# Yugocade.net
KiCad netlist of a schematic drawn in EAGLE
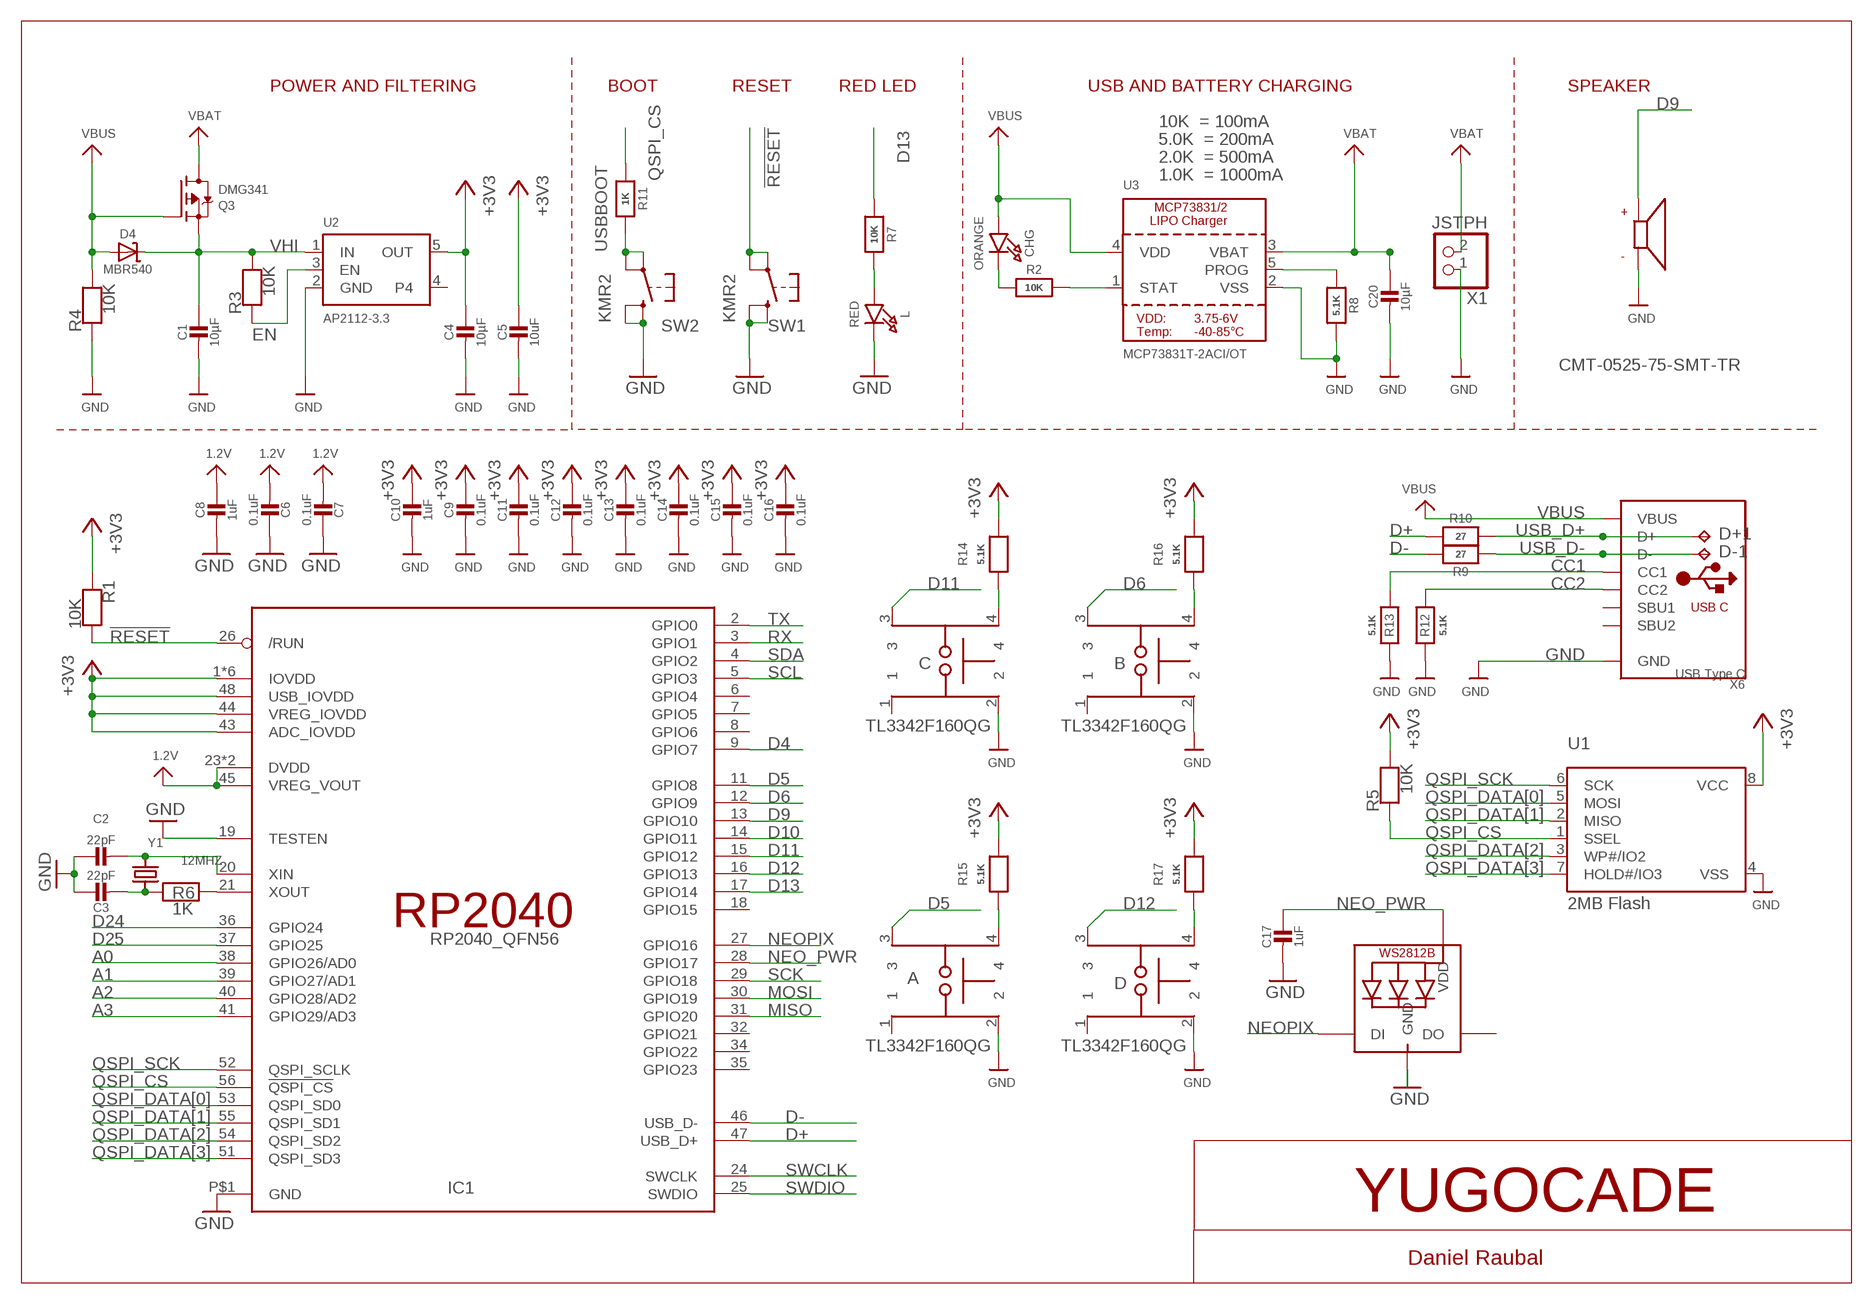
[diagram p0: schematic, sheet 1]

(export (version "E")
  (design (tool "Eeschema 10.0.6"))
  (components
    (comp (ref "A")
      (value "TL3342F160QG")
      (footprint "eagle-import:SW_TL3342F160QG")
      (fields (field (name "MF") "E-Switch"))
      (libsource (lib "eagle-import") (part "TL3342F160QG"))
    )
    (comp (ref "B")
      (value "TL3342F160QG")
      (footprint "eagle-import:SW_TL3342F160QG")
      (fields (field (name "MF") "E-Switch"))
      (libsource (lib "eagle-import") (part "TL3342F160QG"))
    )
    (comp (ref "C")
      (value "TL3342F160QG")
      (footprint "eagle-import:SW_TL3342F160QG")
      (fields (field (name "MF") "E-Switch"))
      (libsource (lib "eagle-import") (part "TL3342F160QG"))
    )
    (comp (ref "C1")
      (value "10µF")
      (footprint "eagle-import:0805-NO")
      (libsource (lib "eagle-import") (part "CAP_CERAMIC0805-NOOUTLINE"))
    )
    (comp (ref "C2")
      (value "22pF")
      (footprint "eagle-import:0603-NO")
      (libsource (lib "eagle-import") (part "CAP_CERAMIC0603_NO"))
    )
    (comp (ref "C3")
      (value "22pF")
      (footprint "eagle-import:0603-NO")
      (libsource (lib "eagle-import") (part "CAP_CERAMIC0603_NO"))
    )
    (comp (ref "C4")
      (value "10µF")
      (footprint "eagle-import:0805-NO")
      (fields (field (name "REV") "A"))
      (libsource (lib "eagle-import") (part "CAP_CERAMIC0805-NOOUTLINE"))
    )
    (comp (ref "C5")
      (value "10uF")
      (footprint "eagle-import:0805-NO")
      (libsource (lib "eagle-import") (part "CAP_CERAMIC0805-NOOUTLINE"))
    )
    (comp (ref "C6")
      (value "0.1uF")
      (footprint "eagle-import:0603-NO")
      (libsource (lib "eagle-import") (part "CAP_CERAMIC0603_NO"))
    )
    (comp (ref "C7")
      (value "0.1uF")
      (footprint "eagle-import:0603-NO")
      (libsource (lib "eagle-import") (part "CAP_CERAMIC0603_NO"))
    )
    (comp (ref "C8")
      (value "1uF")
      (footprint "eagle-import:0603-NO")
      (libsource (lib "eagle-import") (part "CAP_CERAMIC0603_NO"))
    )
    (comp (ref "C9")
      (value "0.1uF")
      (footprint "eagle-import:0603-NO")
      (libsource (lib "eagle-import") (part "CAP_CERAMIC0603_NO"))
    )
    (comp (ref "C10")
      (value "1uF")
      (footprint "eagle-import:0603-NO")
      (libsource (lib "eagle-import") (part "CAP_CERAMIC0603_NO"))
    )
    (comp (ref "C11")
      (value "0.1uF")
      (footprint "eagle-import:0603-NO")
      (libsource (lib "eagle-import") (part "CAP_CERAMIC0603_NO"))
    )
    (comp (ref "C12")
      (value "0.1uF")
      (footprint "eagle-import:0603-NO")
      (libsource (lib "eagle-import") (part "CAP_CERAMIC0603_NO"))
    )
    (comp (ref "C13")
      (value "0.1uF")
      (footprint "eagle-import:0603-NO")
      (libsource (lib "eagle-import") (part "CAP_CERAMIC0603_NO"))
    )
    (comp (ref "C14")
      (value "0.1uF")
      (footprint "eagle-import:0603-NO")
      (libsource (lib "eagle-import") (part "CAP_CERAMIC0603_NO"))
    )
    (comp (ref "C15")
      (value "0.1uF")
      (footprint "eagle-import:0603-NO")
      (libsource (lib "eagle-import") (part "CAP_CERAMIC0603_NO"))
    )
    (comp (ref "C16")
      (value "0.1uF")
      (footprint "eagle-import:0603-NO")
      (libsource (lib "eagle-import") (part "CAP_CERAMIC0603_NO"))
    )
    (comp (ref "C17")
      (value "1uF")
      (footprint "eagle-import:0603-NO")
      (libsource (lib "eagle-import") (part "CAP_CERAMIC0603_NO"))
    )
    (comp (ref "C20")
      (value "10µF")
      (footprint "eagle-import:0805-NO")
      (libsource (lib "eagle-import") (part "CAP_CERAMIC0805-NOOUTLINE"))
    )
    (comp (ref "CHG")
      (value "ORANGE")
      (footprint "eagle-import:CHIPLED_0603_NOOUTLINE")
      (libsource (lib "eagle-import") (part "LED0603_NOOUTLINE"))
    )
    (comp (ref "D")
      (value "TL3342F160QG")
      (footprint "eagle-import:SW_TL3342F160QG")
      (fields (field (name "MF") "E-Switch"))
      (libsource (lib "eagle-import") (part "TL3342F160QG"))
    )
    (comp (ref "D+1")
      (value "TPB1,27")
      (footprint "eagle-import:B1,27")
      (libsource (lib "eagle-import") (part "TPB1,27"))
    )
    (comp (ref "D-1")
      (value "TPB1,27")
      (footprint "eagle-import:B1,27")
      (libsource (lib "eagle-import") (part "TPB1,27"))
    )
    (comp (ref "D4")
      (value "MBR540")
      (footprint "eagle-import:SOD-123")
      (libsource (lib "eagle-import") (part "DIODE-SCHOTTKYSOD-123"))
    )
    (comp (ref "IC1")
      (value "RP2040_QFN56")
      (footprint "eagle-import:QFN56_7MM_REDUCEDEPAD")
      (libsource (lib "eagle-import") (part "RP2040_QFN56"))
    )
    (comp (ref "L")
      (value "RED")
      (footprint "eagle-import:CHIPLED_0603_NOOUTLINE")
      (libsource (lib "eagle-import") (part "LED0603_NOOUTLINE"))
    )
    (comp (ref "LED1")
      (value "WS2812B3535")
      (footprint "eagle-import:LED3535")
      (libsource (lib "eagle-import") (part "WS2812B3535"))
    )
    (comp (ref "LS1")
      (value "CMT-0525-75-SMT-TR")
      (footprint "eagle-import:XDCR_CMT-0525-75-SMT-TR")
      (fields (field (name "MF") "CUI Devices"))
      (libsource (lib "eagle-import") (part "CMT-0525-75-SMT-TR"))
    )
    (comp (ref "Q3")
      (value "DMG341")
      (footprint "eagle-import:SOT23-R")
      (libsource (lib "eagle-import") (part "MOSFET-P"))
    )
    (comp (ref "R1")
      (value "10K")
      (footprint "eagle-import:0603-NO")
      (libsource (lib "eagle-import") (part "RESISTOR_0603_NOOUT"))
    )
    (comp (ref "R2")
      (value "10K")
      (footprint "eagle-import:0603-NO")
      (libsource (lib "eagle-import") (part "RESISTOR_0603_NOOUT"))
    )
    (comp (ref "R3")
      (value "10K")
      (footprint "eagle-import:0603-NO")
      (libsource (lib "eagle-import") (part "RESISTOR_0603_NOOUT"))
    )
    (comp (ref "R4")
      (value "10K")
      (footprint "eagle-import:0603-NO")
      (libsource (lib "eagle-import") (part "RESISTOR_0603_NOOUT"))
    )
    (comp (ref "R5")
      (value "10K")
      (footprint "eagle-import:0603-NO")
      (libsource (lib "eagle-import") (part "RESISTOR_0603_NOOUT"))
    )
    (comp (ref "R6")
      (value "1K")
      (footprint "eagle-import:0603-NO")
      (libsource (lib "eagle-import") (part "RESISTOR_0603_NOOUT"))
    )
    (comp (ref "R7")
      (value "10K")
      (footprint "eagle-import:0603-NO")
      (libsource (lib "eagle-import") (part "RESISTOR_0603_NOOUT"))
    )
    (comp (ref "R8")
      (value "5.1K")
      (footprint "eagle-import:0603-NO")
      (libsource (lib "eagle-import") (part "RESISTOR_0603_NOOUT"))
    )
    (comp (ref "R9")
      (value "27")
      (footprint "eagle-import:0603-NO")
      (libsource (lib "eagle-import") (part "RESISTOR_0603_NOOUT"))
    )
    (comp (ref "R10")
      (value "27")
      (footprint "eagle-import:0603-NO")
      (libsource (lib "eagle-import") (part "RESISTOR_0603_NOOUT"))
    )
    (comp (ref "R11")
      (value "1K")
      (footprint "eagle-import:0603-NO")
      (libsource (lib "eagle-import") (part "RESISTOR_0603_NOOUT"))
    )
    (comp (ref "R12")
      (value "5.1K")
      (footprint "eagle-import:0603-NO")
      (libsource (lib "eagle-import") (part "RESISTOR_0603_NOOUT"))
    )
    (comp (ref "R13")
      (value "5.1K")
      (footprint "eagle-import:0603-NO")
      (libsource (lib "eagle-import") (part "RESISTOR_0603_NOOUT"))
    )
    (comp (ref "R14")
      (value "5.1K")
      (footprint "eagle-import:0603-NO")
      (libsource (lib "eagle-import") (part "RESISTOR_0603_NOOUT"))
    )
    (comp (ref "R15")
      (value "5.1K")
      (footprint "eagle-import:0603-NO")
      (libsource (lib "eagle-import") (part "RESISTOR_0603_NOOUT"))
    )
    (comp (ref "R16")
      (value "5.1K")
      (footprint "eagle-import:0603-NO")
      (libsource (lib "eagle-import") (part "RESISTOR_0603_NOOUT"))
    )
    (comp (ref "R17")
      (value "5.1K")
      (footprint "eagle-import:0603-NO")
      (libsource (lib "eagle-import") (part "RESISTOR_0603_NOOUT"))
    )
    (comp (ref "SW1")
      (value "KMR2")
      (footprint "eagle-import:BTN_KMR2_4.6X2.8")
      (libsource (lib "eagle-import") (part "SWITCH_TACT_SMT4.6X2.8"))
    )
    (comp (ref "SW2")
      (value "KMR2")
      (footprint "eagle-import:BTN_KMR2_4.6X2.8")
      (libsource (lib "eagle-import") (part "SWITCH_TACT_SMT4.6X2.8"))
    )
    (comp (ref "U1")
      (value "2MB Flash")
      (footprint "eagle-import:SOIC8_208MIL")
      (libsource (lib "eagle-import") (part "SPIFLASH_8PIN208MIL"))
    )
    (comp (ref "U2")
      (value "AP2112-3.3")
      (footprint "eagle-import:SOT23-5@1")
      (libsource (lib "eagle-import") (part "VREG_SOT23-5"))
    )
    (comp (ref "U3")
      (value "MCP73831T-2ACI/OT")
      (footprint "eagle-import:SOT23-5")
      (libsource (lib "eagle-import") (part "MCP73831/2"))
    )
    (comp (ref "X1")
      (value "JSTPH")
      (footprint "eagle-import:JSTPH2_BATT")
      (libsource (lib "eagle-import") (part "CON_JST_PH_2PIN_BATT"))
    )
    (comp (ref "X6")
      (value "USB Type C")
      (footprint "eagle-import:USB_C_CUSB31-CFM2AX-01-X")
      (libsource (lib "eagle-import") (part "USB_C"))
    )
    (comp (ref "Y1")
      (value "12MHZ")
      (footprint "eagle-import:CRYSTAL_2.5X2")
      (libsource (lib "eagle-import") (part "CRYSTAL2.5X2.0"))
    )
  )
  (nets
    (net (code "1") (name "+3V3") (class "Default")
      (node (ref "C10") (pin "1") (pinfunction "1_1") (pintype "passive"))
      (node (ref "C11") (pin "1") (pinfunction "1_1") (pintype "passive"))
      (node (ref "C12") (pin "1") (pinfunction "1_1") (pintype "passive"))
      (node (ref "C13") (pin "1") (pinfunction "1_1") (pintype "passive"))
      (node (ref "C14") (pin "1") (pinfunction "1_1") (pintype "passive"))
      (node (ref "C15") (pin "1") (pinfunction "1_1") (pintype "passive"))
      (node (ref "C16") (pin "1") (pinfunction "1_1") (pintype "passive"))
      (node (ref "C4") (pin "1") (pinfunction "1_1") (pintype "passive"))
      (node (ref "C5") (pin "1") (pinfunction "1_1") (pintype "passive"))
      (node (ref "C9") (pin "1") (pinfunction "1_1") (pintype "passive"))
      (node (ref "IC1") (pin "1") (pinfunction "IOVDD_1") (pintype "power_in"))
      (node (ref "IC1") (pin "10") (pinfunction "IOVDD_10") (pintype "power_in"))
      (node (ref "IC1") (pin "22") (pinfunction "IOVDD_22") (pintype "power_in"))
      (node (ref "IC1") (pin "33") (pinfunction "IOVDD_33") (pintype "power_in"))
      (node (ref "IC1") (pin "42") (pinfunction "IOVDD_42") (pintype "power_in"))
      (node (ref "IC1") (pin "43") (pinfunction "ADC_IOVDD_43") (pintype "power_in"))
      (node (ref "IC1") (pin "44") (pinfunction "VREG_IOVDD_44") (pintype "power_in"))
      (node (ref "IC1") (pin "48") (pinfunction "USB_IOVDD_48") (pintype "power_in"))
      (node (ref "IC1") (pin "49") (pinfunction "IOVDD_49") (pintype "power_in"))
      (node (ref "R1") (pin "1") (pinfunction "1_1") (pintype "passive"))
      (node (ref "R14") (pin "1") (pinfunction "1_1") (pintype "passive"))
      (node (ref "R15") (pin "1") (pinfunction "1_1") (pintype "passive"))
      (node (ref "R16") (pin "1") (pinfunction "1_1") (pintype "passive"))
      (node (ref "R17") (pin "1") (pinfunction "1_1") (pintype "passive"))
      (node (ref "R5") (pin "2") (pinfunction "2_2") (pintype "passive"))
      (node (ref "U1") (pin "8") (pinfunction "VCC_8") (pintype "bidirectional"))
      (node (ref "U2") (pin "5") (pinfunction "OUT_5") (pintype "power_in"))
    )
    (net (code "2") (name "/A0") (class "Default")
      (node (ref "IC1") (pin "38") (pinfunction "GPIO26/AD0_38") (pintype "bidirectional"))
    )
    (net (code "3") (name "/A1") (class "Default")
      (node (ref "IC1") (pin "39") (pinfunction "GPIO27/AD1_39") (pintype "bidirectional"))
    )
    (net (code "4") (name "/A2") (class "Default")
      (node (ref "IC1") (pin "40") (pinfunction "GPIO28/AD2_40") (pintype "bidirectional"))
    )
    (net (code "5") (name "/A3") (class "Default")
      (node (ref "IC1") (pin "41") (pinfunction "GPIO29/AD3_41") (pintype "bidirectional"))
    )
    (net (code "6") (name "/CC1") (class "Default")
      (node (ref "R13") (pin "2") (pinfunction "2_2") (pintype "passive"))
      (node (ref "X6") (pin "A5") (pinfunction "CC1_A5") (pintype "bidirectional"))
    )
    (net (code "7") (name "/CC2") (class "Default")
      (node (ref "R12") (pin "2") (pinfunction "2_2") (pintype "passive"))
      (node (ref "X6") (pin "B5") (pinfunction "CC2_B5") (pintype "bidirectional"))
    )
    (net (code "8") (name "/D+") (class "Default")
      (node (ref "IC1") (pin "47") (pinfunction "USB_D+_47") (pintype "bidirectional"))
      (node (ref "R10") (pin "2") (pinfunction "2_2") (pintype "passive"))
    )
    (net (code "9") (name "/D-") (class "Default")
      (node (ref "IC1") (pin "46") (pinfunction "USB_D-_46") (pintype "bidirectional"))
      (node (ref "R9") (pin "2") (pinfunction "2_2") (pintype "passive"))
    )
    (net (code "10") (name "/D4") (class "Default")
      (node (ref "IC1") (pin "9") (pinfunction "GPIO7_9") (pintype "bidirectional"))
    )
    (net (code "11") (name "/D5") (class "Default")
      (node (ref "A") (pin "3") (pinfunction "3_3") (pintype "passive"))
      (node (ref "IC1") (pin "11") (pinfunction "GPIO8_11") (pintype "bidirectional"))
    )
    (net (code "12") (name "/D6") (class "Default")
      (node (ref "B") (pin "3") (pinfunction "3_3") (pintype "passive"))
      (node (ref "IC1") (pin "12") (pinfunction "GPIO9_12") (pintype "bidirectional"))
    )
    (net (code "13") (name "/D9") (class "Default")
      (node (ref "IC1") (pin "13") (pinfunction "GPIO10_13") (pintype "bidirectional"))
      (node (ref "LS1") (pin "P") (pinfunction "P_P") (pintype "passive"))
    )
    (net (code "14") (name "/D10") (class "Default")
      (node (ref "IC1") (pin "14") (pinfunction "GPIO11_14") (pintype "bidirectional"))
    )
    (net (code "15") (name "/D11") (class "Default")
      (node (ref "C") (pin "3") (pinfunction "3_3") (pintype "passive"))
      (node (ref "IC1") (pin "15") (pinfunction "GPIO12_15") (pintype "bidirectional"))
    )
    (net (code "16") (name "/D12") (class "Default")
      (node (ref "D") (pin "3") (pinfunction "3_3") (pintype "passive"))
      (node (ref "IC1") (pin "16") (pinfunction "GPIO13_16") (pintype "bidirectional"))
    )
    (net (code "17") (name "/D13") (class "Default")
      (node (ref "IC1") (pin "17") (pinfunction "GPIO14_17") (pintype "bidirectional"))
      (node (ref "R7") (pin "1") (pinfunction "1_1") (pintype "passive"))
    )
    (net (code "18") (name "/D24") (class "Default")
      (node (ref "IC1") (pin "36") (pinfunction "GPIO24_36") (pintype "bidirectional"))
    )
    (net (code "19") (name "/D25") (class "Default")
      (node (ref "IC1") (pin "37") (pinfunction "GPIO25_37") (pintype "bidirectional"))
    )
    (net (code "20") (name "/EN") (class "Default")
      (node (ref "R3") (pin "1") (pinfunction "1_1") (pintype "passive"))
      (node (ref "U2") (pin "3") (pinfunction "EN_3") (pintype "input"))
    )
    (net (code "21") (name "/MISO") (class "Default")
      (node (ref "IC1") (pin "31") (pinfunction "GPIO20_31") (pintype "bidirectional"))
    )
    (net (code "22") (name "/MOSI") (class "Default")
      (node (ref "IC1") (pin "30") (pinfunction "GPIO19_30") (pintype "bidirectional"))
    )
    (net (code "23") (name "/NEOPIX") (class "Default")
      (node (ref "IC1") (pin "27") (pinfunction "GPIO16_27") (pintype "bidirectional"))
      (node (ref "LED1") (pin "1") (pinfunction "DI_1") (pintype "input"))
    )
    (net (code "24") (name "/NEO_PWR") (class "Default")
      (node (ref "C17") (pin "1") (pinfunction "1_1") (pintype "passive"))
      (node (ref "IC1") (pin "28") (pinfunction "GPIO17_28") (pintype "bidirectional"))
      (node (ref "LED1") (pin "2") (pinfunction "VDD_2") (pintype "power_in"))
    )
    (net (code "25") (name "/QSPI_CS") (class "Default")
      (node (ref "IC1") (pin "56") (pinfunction "~{QSPI_CS}_56") (pintype "bidirectional"))
      (node (ref "R11") (pin "1") (pinfunction "1_1") (pintype "passive"))
      (node (ref "R5") (pin "1") (pinfunction "1_1") (pintype "passive"))
      (node (ref "U1") (pin "1") (pinfunction "SSEL_1") (pintype "bidirectional"))
    )
    (net (code "26") (name "/QSPI_DATA[0]") (class "Default")
      (node (ref "IC1") (pin "53") (pinfunction "QSPI_SD0_53") (pintype "bidirectional"))
      (node (ref "U1") (pin "5") (pinfunction "MOSI_5") (pintype "bidirectional"))
    )
    (net (code "27") (name "/QSPI_DATA[1]") (class "Default")
      (node (ref "IC1") (pin "55") (pinfunction "QSPI_SD1_55") (pintype "bidirectional"))
      (node (ref "U1") (pin "2") (pinfunction "MISO_2") (pintype "bidirectional"))
    )
    (net (code "28") (name "/QSPI_DATA[2]") (class "Default")
      (node (ref "IC1") (pin "54") (pinfunction "QSPI_SD2_54") (pintype "bidirectional"))
      (node (ref "U1") (pin "3") (pinfunction "WP#/IO2_3") (pintype "bidirectional"))
    )
    (net (code "29") (name "/QSPI_DATA[3]") (class "Default")
      (node (ref "IC1") (pin "51") (pinfunction "QSPI_SD3_51") (pintype "bidirectional"))
      (node (ref "U1") (pin "7") (pinfunction "HOLD#/IO3_7") (pintype "bidirectional"))
    )
    (net (code "30") (name "/QSPI_SCK") (class "Default")
      (node (ref "IC1") (pin "52") (pinfunction "QSPI_SCLK_52") (pintype "bidirectional"))
      (node (ref "U1") (pin "6") (pinfunction "SCK_6") (pintype "bidirectional"))
    )
    (net (code "31") (name "/RX") (class "Default")
      (node (ref "IC1") (pin "3") (pinfunction "GPIO1_3") (pintype "bidirectional"))
    )
    (net (code "32") (name "/SCK") (class "Default")
      (node (ref "IC1") (pin "29") (pinfunction "GPIO18_29") (pintype "bidirectional"))
    )
    (net (code "33") (name "/SCL") (class "Default")
      (node (ref "IC1") (pin "5") (pinfunction "GPIO3_5") (pintype "bidirectional"))
    )
    (net (code "34") (name "/SDA") (class "Default")
      (node (ref "IC1") (pin "4") (pinfunction "GPIO2_4") (pintype "bidirectional"))
    )
    (net (code "35") (name "/SWCLK") (class "Default")
      (node (ref "IC1") (pin "24") (pinfunction "SWCLK_24") (pintype "bidirectional"))
    )
    (net (code "36") (name "/SWDIO") (class "Default")
      (node (ref "IC1") (pin "25") (pinfunction "SWDIO_25") (pintype "bidirectional"))
    )
    (net (code "37") (name "/TX") (class "Default")
      (node (ref "IC1") (pin "2") (pinfunction "GPIO0_2") (pintype "bidirectional"))
    )
    (net (code "38") (name "/USBBOOT") (class "Default")
      (node (ref "R11") (pin "2") (pinfunction "2_2") (pintype "passive"))
      (node (ref "SW2") (pin "A") (pinfunction "P_A") (pintype "passive"))
      (node (ref "SW2") (pin "A'") (pinfunction "P1_A'") (pintype "passive"))
    )
    (net (code "39") (name "/USB_D+") (class "Default")
      (node (ref "D+1") (pin "TP") (pinfunction "TP_TP") (pintype "input"))
      (node (ref "R10") (pin "1") (pinfunction "1_1") (pintype "passive"))
      (node (ref "X6") (pin "A6") (pinfunction "D+_A6") (pintype "bidirectional"))
      (node (ref "X6") (pin "B6") (pinfunction "D+_B6") (pintype "bidirectional"))
    )
    (net (code "40") (name "/USB_D-") (class "Default")
      (node (ref "D-1") (pin "TP") (pinfunction "TP_TP") (pintype "input"))
      (node (ref "R9") (pin "1") (pinfunction "1_1") (pintype "passive"))
      (node (ref "X6") (pin "A7") (pinfunction "D-_A7") (pintype "bidirectional"))
      (node (ref "X6") (pin "B7") (pinfunction "D-_B7") (pintype "bidirectional"))
    )
    (net (code "41") (name "/VHI") (class "Default")
      (node (ref "C1") (pin "1") (pinfunction "1_1") (pintype "passive"))
      (node (ref "D4") (pin "C") (pinfunction "C_C") (pintype "passive"))
      (node (ref "Q3") (pin "2") (pinfunction "S_2") (pintype "passive"))
      (node (ref "R3") (pin "2") (pinfunction "2_2") (pintype "passive"))
      (node (ref "U2") (pin "1") (pinfunction "IN_1") (pintype "power_in"))
    )
    (net (code "42") (name "/~{RESET}") (class "Default")
      (node (ref "IC1") (pin "26") (pinfunction "/RUN_26") (pintype "bidirectional"))
      (node (ref "R1") (pin "2") (pinfunction "2_2") (pintype "passive"))
      (node (ref "SW1") (pin "A") (pinfunction "P_A") (pintype "passive"))
      (node (ref "SW1") (pin "A'") (pinfunction "P1_A'") (pintype "passive"))
    )
    (net (code "43") (name "1.2V") (class "Default")
      (node (ref "C6") (pin "2") (pinfunction "2_2") (pintype "passive"))
      (node (ref "C7") (pin "2") (pinfunction "2_2") (pintype "passive"))
      (node (ref "C8") (pin "1") (pinfunction "1_1") (pintype "passive"))
      (node (ref "IC1") (pin "23") (pinfunction "DVDD_23") (pintype "power_in"))
      (node (ref "IC1") (pin "45") (pinfunction "VREG_VOUT_45") (pintype "power_in"))
      (node (ref "IC1") (pin "50") (pinfunction "DVDD_50") (pintype "power_in"))
    )
    (net (code "44") (name "GND") (class "Default")
      (node (ref "A") (pin "2") (pinfunction "2_2") (pintype "passive"))
      (node (ref "B") (pin "2") (pinfunction "2_2") (pintype "passive"))
      (node (ref "C") (pin "2") (pinfunction "2_2") (pintype "passive"))
      (node (ref "C1") (pin "2") (pinfunction "2_2") (pintype "passive"))
      (node (ref "C10") (pin "2") (pinfunction "2_2") (pintype "passive"))
      (node (ref "C11") (pin "2") (pinfunction "2_2") (pintype "passive"))
      (node (ref "C12") (pin "2") (pinfunction "2_2") (pintype "passive"))
      (node (ref "C13") (pin "2") (pinfunction "2_2") (pintype "passive"))
      (node (ref "C14") (pin "2") (pinfunction "2_2") (pintype "passive"))
      (node (ref "C15") (pin "2") (pinfunction "2_2") (pintype "passive"))
      (node (ref "C16") (pin "2") (pinfunction "2_2") (pintype "passive"))
      (node (ref "C17") (pin "2") (pinfunction "2_2") (pintype "passive"))
      (node (ref "C2") (pin "1") (pinfunction "1_1") (pintype "passive"))
      (node (ref "C20") (pin "2") (pinfunction "2_2") (pintype "passive"))
      (node (ref "C3") (pin "1") (pinfunction "1_1") (pintype "passive"))
      (node (ref "C4") (pin "2") (pinfunction "2_2") (pintype "passive"))
      (node (ref "C5") (pin "2") (pinfunction "2_2") (pintype "passive"))
      (node (ref "C6") (pin "1") (pinfunction "1_1") (pintype "passive"))
      (node (ref "C7") (pin "1") (pinfunction "1_1") (pintype "passive"))
      (node (ref "C8") (pin "2") (pinfunction "2_2") (pintype "passive"))
      (node (ref "C9") (pin "2") (pinfunction "2_2") (pintype "passive"))
      (node (ref "D") (pin "2") (pinfunction "2_2") (pintype "passive"))
      (node (ref "IC1") (pin "19") (pinfunction "TESTEN_19") (pintype "input"))
      (node (ref "IC1") (pin "P$1") (pinfunction "GND_P$1") (pintype "power_in"))
      (node (ref "L") (pin "C") (pinfunction "C_C") (pintype "passive"))
      (node (ref "LED1") (pin "4") (pinfunction "GND_4") (pintype "power_in"))
      (node (ref "LS1") (pin "N") (pinfunction "N_N") (pintype "passive"))
      (node (ref "R12") (pin "1") (pinfunction "1_1") (pintype "passive"))
      (node (ref "R13") (pin "1") (pinfunction "1_1") (pintype "passive"))
      (node (ref "R4") (pin "1") (pinfunction "1_1") (pintype "passive"))
      (node (ref "R8") (pin "2") (pinfunction "2_2") (pintype "passive"))
      (node (ref "SW1") (pin "B") (pinfunction "S_B") (pintype "passive"))
      (node (ref "SW1") (pin "B'") (pinfunction "S1_B'") (pintype "passive"))
      (node (ref "SW2") (pin "B") (pinfunction "S_B") (pintype "passive"))
      (node (ref "SW2") (pin "B'") (pinfunction "S1_B'") (pintype "passive"))
      (node (ref "U1") (pin "4") (pinfunction "VSS_4") (pintype "bidirectional"))
      (node (ref "U2") (pin "2") (pinfunction "GND_2") (pintype "power_in"))
      (node (ref "U3") (pin "2") (pinfunction "VSS_2") (pintype "power_in"))
      (node (ref "X1") (pin "1") (pinfunction "1_1") (pintype "passive"))
      (node (ref "X6") (pin "A1B12") (pinfunction "GND_A1B12") (pintype "power_in"))
      (node (ref "X6") (pin "B1A12") (pinfunction "GND_B1A12") (pintype "power_in"))
    )
    (net (code "45") (name "Net-(A-Pad4)") (class "Default")
      (node (ref "A") (pin "4") (pinfunction "4_4") (pintype "passive"))
      (node (ref "R15") (pin "2") (pinfunction "2_2") (pintype "passive"))
    )
    (net (code "46") (name "Net-(B-Pad4)") (class "Default")
      (node (ref "B") (pin "4") (pinfunction "4_4") (pintype "passive"))
      (node (ref "R16") (pin "2") (pinfunction "2_2") (pintype "passive"))
    )
    (net (code "47") (name "Net-(C-Pad4)") (class "Default")
      (node (ref "C") (pin "4") (pinfunction "4_4") (pintype "passive"))
      (node (ref "R14") (pin "2") (pinfunction "2_2") (pintype "passive"))
    )
    (net (code "48") (name "Net-(C3-Pad2)") (class "Default")
      (node (ref "C3") (pin "2") (pinfunction "2_2") (pintype "passive"))
      (node (ref "R6") (pin "1") (pinfunction "1_1") (pintype "passive"))
      (node (ref "Y1") (pin "1") (pinfunction "1_1") (pintype "passive"))
    )
    (net (code "49") (name "Net-(CHG-PadC)") (class "Default")
      (node (ref "CHG") (pin "C") (pinfunction "C_C") (pintype "passive"))
      (node (ref "R2") (pin "1") (pinfunction "1_1") (pintype "passive"))
    )
    (net (code "50") (name "Net-(D-Pad4)") (class "Default")
      (node (ref "D") (pin "4") (pinfunction "4_4") (pintype "passive"))
      (node (ref "R17") (pin "2") (pinfunction "2_2") (pintype "passive"))
    )
    (net (code "51") (name "Net-(IC1-XIN)") (class "Default")
      (node (ref "C2") (pin "2") (pinfunction "2_2") (pintype "passive"))
      (node (ref "IC1") (pin "20") (pinfunction "XIN_20") (pintype "input"))
      (node (ref "Y1") (pin "3") (pinfunction "2_3") (pintype "passive"))
    )
    (net (code "52") (name "Net-(IC1-XOUT)") (class "Default")
      (node (ref "IC1") (pin "21") (pinfunction "XOUT_21") (pintype "output"))
      (node (ref "R6") (pin "2") (pinfunction "2_2") (pintype "passive"))
    )
    (net (code "53") (name "Net-(L-PadA)") (class "Default")
      (node (ref "L") (pin "A") (pinfunction "A_A") (pintype "passive"))
      (node (ref "R7") (pin "2") (pinfunction "2_2") (pintype "passive"))
    )
    (net (code "54") (name "Net-(U3-PROG)") (class "Default")
      (node (ref "R8") (pin "1") (pinfunction "1_1") (pintype "passive"))
      (node (ref "U3") (pin "5") (pinfunction "PROG_5") (pintype "input"))
    )
    (net (code "55") (name "Net-(U3-STAT)") (class "Default")
      (node (ref "R2") (pin "2") (pinfunction "2_2") (pintype "passive"))
      (node (ref "U3") (pin "1") (pinfunction "STAT_1") (pintype "output"))
    )
    (net (code "56") (name "VBAT") (class "Default")
      (node (ref "C20") (pin "1") (pinfunction "1_1") (pintype "passive"))
      (node (ref "Q3") (pin "3") (pinfunction "D_3") (pintype "passive"))
      (node (ref "U3") (pin "3") (pinfunction "VBAT_3") (pintype "power_in"))
      (node (ref "X1") (pin "2") (pinfunction "2_2") (pintype "passive"))
    )
    (net (code "57") (name "VBUS") (class "Default")
      (node (ref "CHG") (pin "A") (pinfunction "A_A") (pintype "passive"))
      (node (ref "D4") (pin "A") (pinfunction "A_A") (pintype "passive"))
      (node (ref "Q3") (pin "1") (pinfunction "G_1") (pintype "passive"))
      (node (ref "R4") (pin "2") (pinfunction "2_2") (pintype "passive"))
      (node (ref "U3") (pin "4") (pinfunction "VDD_4") (pintype "power_in"))
      (node (ref "X6") (pin "A4B9") (pinfunction "VBUS_A4B9") (pintype "power_in"))
      (node (ref "X6") (pin "B4A9") (pinfunction "VBUS_B4A9") (pintype "power_in"))
    )
    (net (code "58") (name "unconnected-(A-Pad1)") (class "Default")
      (node (ref "A") (pin "1") (pinfunction "1_1") (pintype "passive"))
    )
    (net (code "59") (name "unconnected-(B-Pad1)") (class "Default")
      (node (ref "B") (pin "1") (pinfunction "1_1") (pintype "passive"))
    )
    (net (code "60") (name "unconnected-(C-Pad1)") (class "Default")
      (node (ref "C") (pin "1") (pinfunction "1_1") (pintype "passive"))
    )
    (net (code "61") (name "unconnected-(D-Pad1)") (class "Default")
      (node (ref "D") (pin "1") (pinfunction "1_1") (pintype "passive"))
    )
    (net (code "62") (name "unconnected-(IC1-GPIO4-Pad6)") (class "Default")
      (node (ref "IC1") (pin "6") (pinfunction "GPIO4_6") (pintype "bidirectional"))
    )
    (net (code "63") (name "unconnected-(IC1-GPIO5-Pad7)") (class "Default")
      (node (ref "IC1") (pin "7") (pinfunction "GPIO5_7") (pintype "bidirectional"))
    )
    (net (code "64") (name "unconnected-(IC1-GPIO6-Pad8)") (class "Default")
      (node (ref "IC1") (pin "8") (pinfunction "GPIO6_8") (pintype "bidirectional"))
    )
    (net (code "65") (name "unconnected-(IC1-GPIO15-Pad18)") (class "Default")
      (node (ref "IC1") (pin "18") (pinfunction "GPIO15_18") (pintype "bidirectional"))
    )
    (net (code "66") (name "unconnected-(IC1-GPIO21-Pad32)") (class "Default")
      (node (ref "IC1") (pin "32") (pinfunction "GPIO21_32") (pintype "bidirectional"))
    )
    (net (code "67") (name "unconnected-(IC1-GPIO22-Pad34)") (class "Default")
      (node (ref "IC1") (pin "34") (pinfunction "GPIO22_34") (pintype "bidirectional"))
    )
    (net (code "68") (name "unconnected-(IC1-GPIO23-Pad35)") (class "Default")
      (node (ref "IC1") (pin "35") (pinfunction "GPIO23_35") (pintype "bidirectional"))
    )
    (net (code "69") (name "unconnected-(LED1-DO-Pad3)") (class "Default")
      (node (ref "LED1") (pin "3") (pinfunction "DO_3") (pintype "output"))
    )
    (net (code "70") (name "unconnected-(U2-P4-Pad4)") (class "Default")
      (node (ref "U2") (pin "4") (pinfunction "P4_4") (pintype "bidirectional"))
    )
    (net (code "71") (name "unconnected-(X6-SBU1-PadA8)") (class "Default")
      (node (ref "X6") (pin "A8") (pinfunction "SBU1_A8") (pintype "bidirectional"))
    )
    (net (code "72") (name "unconnected-(X6-SBU2-PadB8)") (class "Default")
      (node (ref "X6") (pin "B8") (pinfunction "SBU2_B8") (pintype "bidirectional"))
    )
  )
)
